# Sheet1.net
KiCad netlist of a schematic drawn in Altium Designer
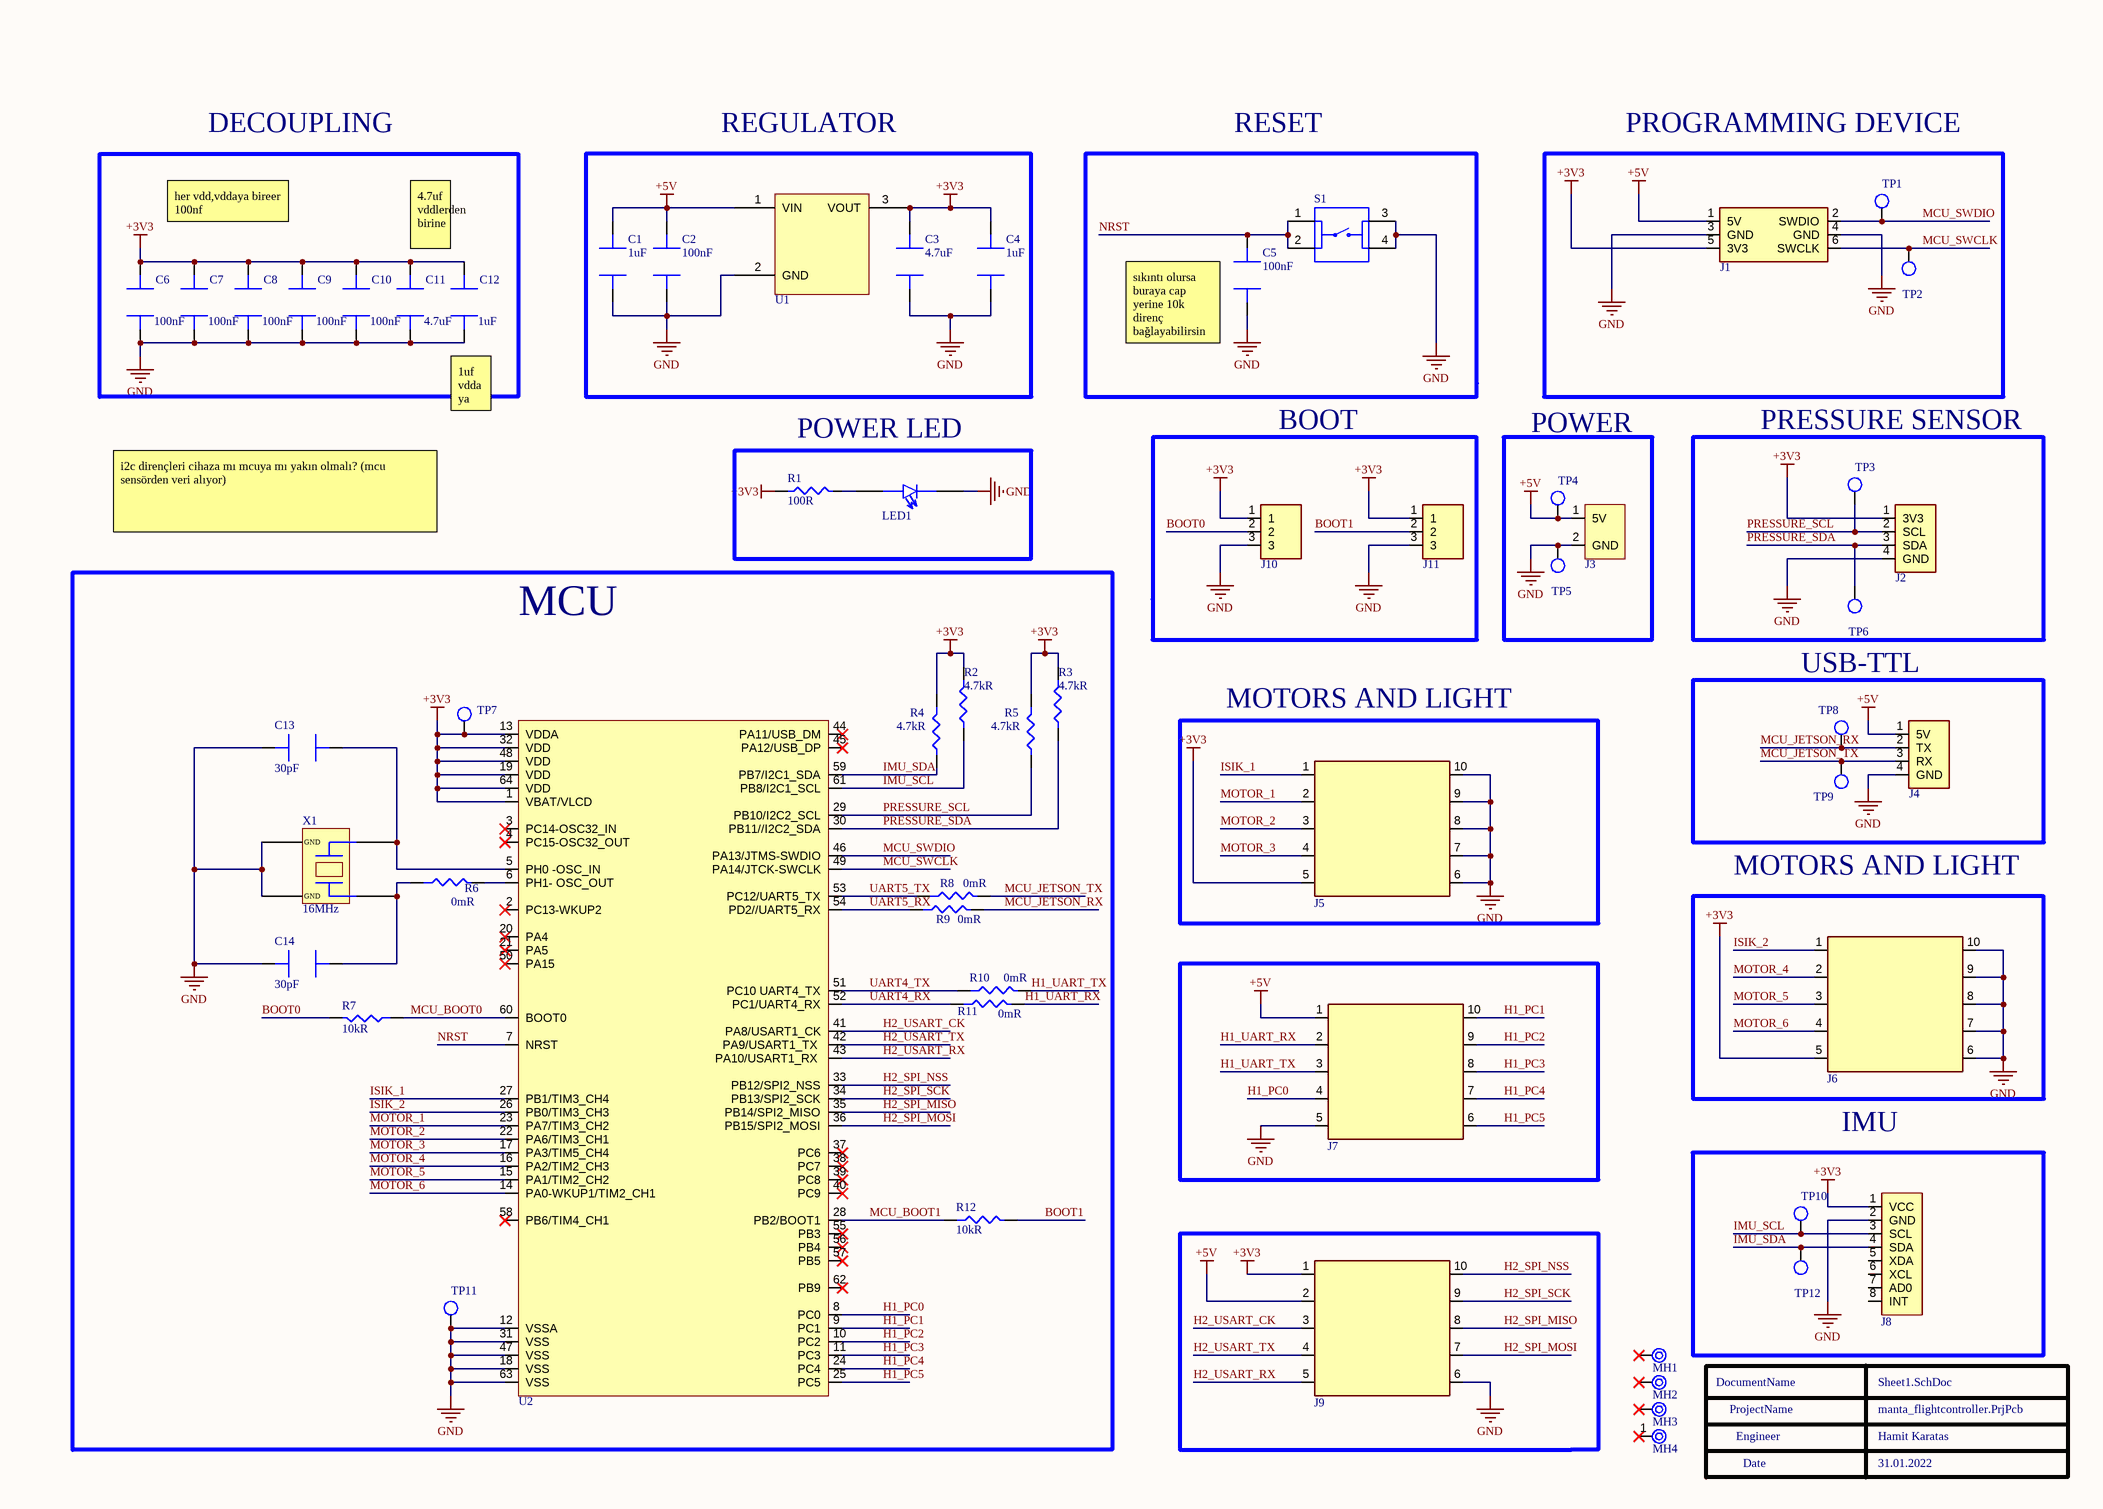
[diagram p0: Sheet1.SchDoc]

(export (version "E")
  (design (tool "Eeschema 10.0.6"))
  (components
    (comp (ref "C1")
      (value "CAP CER 1uF 0805")
      (footprint "cap_0805")
      (description "0805 0.1 uF ±10 % Tolerance 50 V X7R Multilayer Ceramic Capacitors")
      (fields
        (field (name "MANUFACTURER") "Samsung")
        (field (name "MANUFACTURER PART NUMBER") "CL21B104KBFNNNE")
        (field (name "CAPACITANCE") "1uF")
        (field (name "DESIGNED BY") "Hamit")
      )
      (libsource (lib "altium_giris") (part "CAP CER 1uF 0805"))
    )
    (comp (ref "C2")
      (value "CL21B104KBCNNNC")
      (footprint "cap_0805")
      (fields
        (field (name "MANUFACTURER") "Samsung")
        (field (name "TOLERANCE") "10%")
        (field (name "VOLTAGE") "50V")
        (field (name "CAPACITANCE") "100nF")
        (field (name "DESIGNED BY") "Hamit")
      )
      (libsource (lib "altium_giris") (part "CAP cer 100nF 0805"))
    )
    (comp (ref "C3")
      (value "CL21A475KAQNNNE")
      (footprint "cap_0805")
      (fields
        (field (name "MANUFACTURER") "Samsung")
        (field (name "TOLERANCE") "10%")
        (field (name "CAPACITANCE") "4.7uF")
        (field (name "DESIGNED BY") "Hamit")
      )
      (libsource (lib "altium_giris") (part "CAP_0805_4.7uF"))
    )
    (comp (ref "C4")
      (value "CAP CER 1uF 0805")
      (footprint "cap_0805")
      (description "0805 0.1 uF ±10 % Tolerance 50 V X7R Multilayer Ceramic Capacitors")
      (fields
        (field (name "MANUFACTURER") "Samsung")
        (field (name "MANUFACTURER PART NUMBER") "CL21B104KBFNNNE")
        (field (name "CAPACITANCE") "1uF")
        (field (name "DESIGNED BY") "Hamit")
      )
      (libsource (lib "altium_giris") (part "CAP CER 1uF 0805"))
    )
    (comp (ref "C5")
      (value "CAP CER 100nF 0603")
      (footprint "CAP_0603")
      (fields
        (field (name "MANUFACTURER") "KEMET")
        (field (name "MANUFACTURER PART NUMBER") "C0603C104K5RACTU")
        (field (name "TOLERANCE") "10%")
        (field (name "CAPACITANCE") "100nF")
        (field (name "DESIGNED BY") "Hamit")
      )
      (libsource (lib "altium_giris") (part "CAP CER 100nF 0603"))
    )
    (comp (ref "C6")
      (value "CAP CER 100nF 0603")
      (footprint "CAP_0603")
      (fields
        (field (name "MANUFACTURER") "KEMET")
        (field (name "MANUFACTURER PART NUMBER") "C0603C104K5RACTU")
        (field (name "TOLERANCE") "10%")
        (field (name "CAPACITANCE") "100nF")
        (field (name "DESIGNED BY") "Hamit")
      )
      (libsource (lib "altium_giris") (part "CAP CER 100nF 0603"))
    )
    (comp (ref "C7")
      (value "CAP CER 100nF 0603")
      (footprint "CAP_0603")
      (fields
        (field (name "MANUFACTURER") "KEMET")
        (field (name "MANUFACTURER PART NUMBER") "C0603C104K5RACTU")
        (field (name "TOLERANCE") "10%")
        (field (name "CAPACITANCE") "100nF")
        (field (name "DESIGNED BY") "Hamit")
      )
      (libsource (lib "altium_giris") (part "CAP CER 100nF 0603"))
    )
    (comp (ref "C8")
      (value "CAP CER 100nF 0603")
      (footprint "CAP_0603")
      (fields
        (field (name "MANUFACTURER") "KEMET")
        (field (name "MANUFACTURER PART NUMBER") "C0603C104K5RACTU")
        (field (name "TOLERANCE") "10%")
        (field (name "CAPACITANCE") "100nF")
        (field (name "DESIGNED BY") "Hamit")
      )
      (libsource (lib "altium_giris") (part "CAP CER 100nF 0603"))
    )
    (comp (ref "C9")
      (value "CAP CER 100nF 0603")
      (footprint "CAP_0603")
      (fields
        (field (name "MANUFACTURER") "KEMET")
        (field (name "MANUFACTURER PART NUMBER") "C0603C104K5RACTU")
        (field (name "TOLERANCE") "10%")
        (field (name "CAPACITANCE") "100nF")
        (field (name "DESIGNED BY") "Hamit")
      )
      (libsource (lib "altium_giris") (part "CAP CER 100nF 0603"))
    )
    (comp (ref "C10")
      (value "CAP CER 100nF 0603")
      (footprint "CAP_0603")
      (fields
        (field (name "MANUFACTURER") "KEMET")
        (field (name "MANUFACTURER PART NUMBER") "C0603C104K5RACTU")
        (field (name "TOLERANCE") "10%")
        (field (name "CAPACITANCE") "100nF")
        (field (name "DESIGNED BY") "Hamit")
      )
      (libsource (lib "altium_giris") (part "CAP CER 100nF 0603"))
    )
    (comp (ref "C11")
      (value "CL21A475KAQNNNE")
      (footprint "cap_0805")
      (fields
        (field (name "MANUFACTURER") "Samsung")
        (field (name "TOLERANCE") "10%")
        (field (name "CAPACITANCE") "4.7uF")
        (field (name "DESIGNED BY") "Hamit")
      )
      (libsource (lib "altium_giris") (part "CAP CER 4.7 uF"))
    )
    (comp (ref "C12")
      (value "CAP CER 1uF 0805")
      (footprint "cap_0805")
      (description "0805 0.1 uF ±10 % Tolerance 50 V X7R Multilayer Ceramic Capacitors")
      (fields
        (field (name "MANUFACTURER") "Samsung")
        (field (name "MANUFACTURER PART NUMBER") "CL21B104KBFNNNE")
        (field (name "CAPACITANCE") "1uF")
        (field (name "DESIGNED BY") "Hamit")
      )
      (libsource (lib "altium_giris") (part "CAP CER 1uF 0805"))
    )
    (comp (ref "C13")
      (value "C0805C300M5HAC7800")
      (footprint "cap_0805")
      (description "Cap Cer 0805 30PF 50V Ultra Stab")
      (fields (field (name "MANUFACTURER") "KEMET") (field (name "CAPACITANCE") "30pF"))
      (libsource (lib "altium_giris") (part "CAP CER 30 PF 0805"))
    )
    (comp (ref "C14")
      (value "C0805C300M5HAC7800")
      (footprint "cap_0805")
      (description "Cap Cer 0805 30PF 50V Ultra Stab")
      (fields (field (name "MANUFACTURER") "KEMET") (field (name "CAPACITANCE") "30pF"))
      (libsource (lib "altium_giris") (part "CAP CER 30 PF 0805"))
    )
    (comp (ref "J1")
      (value "67997-206HLF")
      (footprint "CONN 6 PINS 2 ROWS")
      (description "Conn Unshrouded Header HDR 6 POS 2.54mm Solder ST Top Entry Thru-Hole BergStik® Bulk")
      (fields (field (name "MANUFACTURER") "ICC"))
      (libsource (lib "altium_giris") (part "CONN 6 PIN 2 ROWS"))
    )
    (comp (ref "J2")
      (value "61300411121")
      (footprint "CONN 4PINS 1 ROW")
      (description "CONN HEADER 4 POS 2.54")
      (fields (field (name "MANUFACTURER") "Wurth Electronics"))
      (libsource (lib "altium_giris") (part "CONN 4 PINS 1 ROW"))
    )
    (comp (ref "J3")
      (value "TERMINAL BLOCK, PLUGGABLE, 5.08,")
      (footprint "TBP01R1-508-02BE")
      (description "Conn Shrouded Header HDR 2 POS 5.08mm Solder RA Side Entry Thru-Hole Bag")
      (fields
        (field (name "MANUFACTURER") "CUI")
        (field (name "MANUFACTURER PART NUMBER") "TBP01R1-508-02BE")
        (field (name "DESIGNED BY") "Hamit")
      )
      (libsource (lib "altium_giris") (part "TERMINAL BLOCK TBP01R1-508-02BE"))
    )
    (comp (ref "J4")
      (value "61300411121")
      (footprint "CONN 4PINS 1 ROW")
      (description "CONN HEADER 4 POS 2.54")
      (fields (field (name "MANUFACTURER") "Wurth Electronics"))
      (libsource (lib "altium_giris") (part "CONN 4 PINS 1 ROW"))
    )
    (comp (ref "J5")
      (value "302-S101")
      (footprint "CONN 10 PINS 2 ROWS")
      (description "10 pin 接头，有罩 连接器 0.100&quot;（2.54mm） 通孔 金")
      (fields (field (name "MANUFACTURER") "On-Shore Technology"))
      (libsource (lib "altium_giris") (part "CONN 10 PINS"))
    )
    (comp (ref "J6")
      (value "302-S101")
      (footprint "CONN 10 PINS 2 ROWS")
      (description "10 pin 接头，有罩 连接器 0.100&quot;（2.54mm） 通孔 金")
      (fields (field (name "MANUFACTURER") "On-Shore Technology"))
      (libsource (lib "altium_giris") (part "CONN 10 PINS"))
    )
    (comp (ref "J7")
      (value "302-S101")
      (footprint "CONN 10 PINS 2 ROWS")
      (description "10 pin 接头，有罩 连接器 0.100&quot;（2.54mm） 通孔 金")
      (fields (field (name "MANUFACTURER") "On-Shore Technology"))
      (libsource (lib "altium_giris") (part "CONN 10 PINS"))
    )
    (comp (ref "J8")
      (value "CONN 8 PIN")
      (footprint "CONN 8 PINS TH 2.54mm")
      (libsource (lib "altium_giris") (part "CONN 8 PIN"))
    )
    (comp (ref "J9")
      (value "302-S101")
      (footprint "CONN 10 PINS 2 ROWS")
      (description "10 pin 接头，有罩 连接器 0.100&quot;（2.54mm） 通孔 金")
      (fields (field (name "MANUFACTURER") "On-Shore Technology"))
      (libsource (lib "altium_giris") (part "CONN 10 PINS"))
    )
    (comp (ref "J10")
      (value "Conn Header HDR 3 POS 2.54mm")
      (footprint "CONN 3 PINS")
      (description "Conn Unshrouded Header HDR 3 POS 2.54mm Solder ST Top Entry Thru-Hole BergStik® Bulk")
      (fields
        (field (name "MANUFACTURER") "Amphenol ICC / FCI")
        (field (name "MANUFACTURER PART NUMBER") "68001-203HLF")
      )
      (libsource (lib "altium_giris") (part "CONN 3 PINS"))
    )
    (comp (ref "J11")
      (value "Conn Header HDR 3 POS 2.54mm")
      (footprint "CONN 3 PINS")
      (description "Conn Unshrouded Header HDR 3 POS 2.54mm Solder ST Top Entry Thru-Hole BergStik® Bulk")
      (fields
        (field (name "MANUFACTURER") "Amphenol ICC / FCI")
        (field (name "MANUFACTURER PART NUMBER") "68001-203HLF")
      )
      (libsource (lib "altium_giris") (part "CONN 3 PINS"))
    )
    (comp (ref "LED1")
      (value "LTST-C171GKT")
      (footprint "LED GREEN 0805")
      (description "Green 0805 130 º Min 5 mcd Typical 12 mcd Water Clear Lens SMT LED")
      (fields (field (name "MANUFACTURER") "Vishay Lite-On") (field (name "DESIGNED BY") "Hamit"))
      (libsource (lib "altium_giris") (part "LED GREEN 0805"))
    )
    (comp (ref "MH1")
      (value "MOUNTING HOLE")
      (footprint "MOUNTING HOLE")
      (libsource (lib "altium_giris") (part "MOUNTING HOLE"))
    )
    (comp (ref "MH2")
      (value "MOUNTING HOLE")
      (footprint "MOUNTING HOLE")
      (libsource (lib "altium_giris") (part "MOUNTING HOLE"))
    )
    (comp (ref "MH3")
      (value "MOUNTING HOLE")
      (footprint "MOUNTING HOLE")
      (libsource (lib "altium_giris") (part "MOUNTING HOLE"))
    )
    (comp (ref "MH4")
      (value "MOUNTING HOLE")
      (footprint "MOUNTING HOLE")
      (libsource (lib "") (part "MOUNTING HOLE_1"))
    )
    (comp (ref "R1")
      (value "RC0603FR-7W100RL")
      (footprint "RES_0603")
      (description "RESISTOR, 0603, 100R, 1%")
      (fields
        (field (name "MANUFACTURER") "Yageo")
        (field (name "TOLERANCE") "1%")
        (field (name "RESISTANCE") "100R")
      )
      (libsource (lib "altium_giris") (part "RES 100 OHM 0603"))
    )
    (comp (ref "R2")
      (value "RC0603JR-074K7L")
      (footprint "res_1206")
      (description "Res Thick Film 0603 4.7K Ohm 5% 0.1W(1/10W) ±100ppm/C Molded SMD Paper T/R")
      (fields
        (field (name "MANUFACTURER") "Yageo")
        (field (name "TOLERANCE") "5%")
        (field (name "RESISTANCE") "4.7kR")
        (field (name "DESIGNED BY") "Hamit")
      )
      (libsource (lib "altium_giris") (part "RES 4K7 OHM"))
    )
    (comp (ref "R3")
      (value "RC0603JR-074K7L")
      (footprint "res_1206")
      (description "Res Thick Film 0603 4.7K Ohm 5% 0.1W(1/10W) ±100ppm/C Molded SMD Paper T/R")
      (fields
        (field (name "MANUFACTURER") "Yageo")
        (field (name "TOLERANCE") "5%")
        (field (name "RESISTANCE") "4.7kR")
        (field (name "DESIGNED BY") "Hamit")
      )
      (libsource (lib "altium_giris") (part "RES 4K7 OHM"))
    )
    (comp (ref "R4")
      (value "RC0603JR-074K7L")
      (footprint "res_1206")
      (description "Res Thick Film 0603 4.7K Ohm 5% 0.1W(1/10W) ±100ppm/C Molded SMD Paper T/R")
      (fields
        (field (name "MANUFACTURER") "Yageo")
        (field (name "TOLERANCE") "5%")
        (field (name "RESISTANCE") "4.7kR")
        (field (name "DESIGNED BY") "Hamit")
      )
      (libsource (lib "altium_giris") (part "RES 4K7 OHM"))
    )
    (comp (ref "R5")
      (value "RC0603JR-074K7L")
      (footprint "res_1206")
      (description "Res Thick Film 0603 4.7K Ohm 5% 0.1W(1/10W) ±100ppm/C Molded SMD Paper T/R")
      (fields
        (field (name "MANUFACTURER") "Yageo")
        (field (name "TOLERANCE") "5%")
        (field (name "RESISTANCE") "4.7kR")
        (field (name "DESIGNED BY") "Hamit")
      )
      (libsource (lib "altium_giris") (part "RES 4K7 OHM"))
    )
    (comp (ref "R6")
      (value "RC0603JR-070RL")
      (footprint "RES_0603")
      (description "RES SMD 0 OHM JUMPER 1/10W 0603")
      (fields
        (field (name "MANUFACTURER") "Yageo")
        (field (name "TOLERANCE") "1%")
        (field (name "RESISTANCE") "0mR")
        (field (name "DESIGNED BY") "Hamit")
      )
      (libsource (lib "altium_giris") (part "RES 0 ohm 0603"))
    )
    (comp (ref "R7")
      (value "RES 10K OHM 0603")
      (footprint "RES_0603")
      (description "Res General Purpose Thick Film 0603 10K Ohm 1% 1/10W ±100ppm/°C Molded SMD Paper T/R")
      (fields
        (field (name "MANUFACTURER") "Yageo")
        (field (name "MANUFACTURER PART NUMBER") "RC0603FR-0710KL")
        (field (name "RESISTANCE") "10kR")
        (field (name "DESIGNED BY") "Hamit")
      )
      (libsource (lib "altium_giris") (part "RES 10K OHM 0603"))
    )
    (comp (ref "R8")
      (value "RC0603JR-070RL")
      (footprint "RES_0603")
      (description "RES SMD 0 OHM JUMPER 1/10W 0603")
      (fields
        (field (name "MANUFACTURER") "Yageo")
        (field (name "TOLERANCE") "1%")
        (field (name "RESISTANCE") "0mR")
        (field (name "DESIGNED BY") "Hamit")
      )
      (libsource (lib "altium_giris") (part "RES 0 ohm 0603"))
    )
    (comp (ref "R9")
      (value "RC0603JR-070RL")
      (footprint "RES_0603")
      (description "RES SMD 0 OHM JUMPER 1/10W 0603")
      (fields
        (field (name "MANUFACTURER") "Yageo")
        (field (name "TOLERANCE") "1%")
        (field (name "RESISTANCE") "0mR")
        (field (name "DESIGNED BY") "Hamit")
      )
      (libsource (lib "altium_giris") (part "RES 0 ohm 0603"))
    )
    (comp (ref "R10")
      (value "RC0603JR-070RL")
      (footprint "RES_0603")
      (description "RES SMD 0 OHM JUMPER 1/10W 0603")
      (fields
        (field (name "MANUFACTURER") "Yageo")
        (field (name "TOLERANCE") "1%")
        (field (name "RESISTANCE") "0mR")
        (field (name "DESIGNED BY") "Hamit")
      )
      (libsource (lib "altium_giris") (part "RES 0 ohm 0603"))
    )
    (comp (ref "R11")
      (value "RC0603JR-070RL")
      (footprint "RES_0603")
      (description "RES SMD 0 OHM JUMPER 1/10W 0603")
      (fields
        (field (name "MANUFACTURER") "Yageo")
        (field (name "TOLERANCE") "1%")
        (field (name "RESISTANCE") "0mR")
        (field (name "DESIGNED BY") "Hamit")
      )
      (libsource (lib "altium_giris") (part "RES 0 ohm 0603"))
    )
    (comp (ref "R12")
      (value "RES 10K OHM 0603")
      (footprint "RES_0603")
      (description "Res General Purpose Thick Film 0603 10K Ohm 1% 1/10W ±100ppm/°C Molded SMD Paper T/R")
      (fields
        (field (name "MANUFACTURER") "Yageo")
        (field (name "MANUFACTURER PART NUMBER") "RC0603FR-0710KL")
        (field (name "RESISTANCE") "10kR")
        (field (name "DESIGNED BY") "Hamit")
      )
      (libsource (lib "altium_giris") (part "RES 10K OHM 0603"))
    )
    (comp (ref "S1")
      (value "1825910-6")
      (footprint "button")
      (description "Switch Tactile OFF (ON) SPST Round Button PC Pins 0.05A 24VDC 1.57N Thru-Hole Loose")
      (fields (field (name "MANUFACTURER") "TE Connectivity Alcoswitch"))
      (libsource (lib "altium_giris") (part "button 4 pads"))
    )
    (comp (ref "TP1")
      (value "TEST_POINT")
      (footprint "TEST POINT")
      (libsource (lib "altium_giris") (part "TEST POINT"))
    )
    (comp (ref "TP2")
      (value "TEST_POINT")
      (footprint "TEST POINT")
      (libsource (lib "altium_giris") (part "TEST POINT"))
    )
    (comp (ref "TP3")
      (value "TEST_POINT")
      (footprint "TEST POINT")
      (libsource (lib "altium_giris") (part "TEST POINT"))
    )
    (comp (ref "TP4")
      (value "TEST_POINT")
      (footprint "TEST POINT")
      (libsource (lib "altium_giris") (part "TEST POINT"))
    )
    (comp (ref "TP5")
      (value "TEST_POINT")
      (footprint "TEST POINT")
      (libsource (lib "altium_giris") (part "TEST POINT"))
    )
    (comp (ref "TP6")
      (value "TEST_POINT")
      (footprint "TEST POINT")
      (libsource (lib "altium_giris") (part "TEST POINT"))
    )
    (comp (ref "TP7")
      (value "TEST_POINT")
      (footprint "TEST POINT")
      (libsource (lib "altium_giris") (part "TEST POINT"))
    )
    (comp (ref "TP8")
      (value "TEST_POINT")
      (footprint "TEST POINT")
      (libsource (lib "altium_giris") (part "TEST POINT"))
    )
    (comp (ref "TP9")
      (value "TEST_POINT")
      (footprint "TEST POINT")
      (libsource (lib "altium_giris") (part "TEST POINT"))
    )
    (comp (ref "TP10")
      (value "TEST_POINT")
      (footprint "TEST POINT")
      (libsource (lib "altium_giris") (part "TEST POINT"))
    )
    (comp (ref "TP11")
      (value "TEST_POINT")
      (footprint "TEST POINT")
      (libsource (lib "altium_giris") (part "TEST POINT"))
    )
    (comp (ref "TP12")
      (value "TEST_POINT")
      (footprint "TEST POINT")
      (libsource (lib "altium_giris") (part "TEST POINT"))
    )
    (comp (ref "U1")
      (value "AP7361-33E-13")
      (footprint "AP7361-33E-13")
      (description "LDO Regulator Pos 3.3V 1A 4-Pin(3+Tab) SOT-223 T/R")
      (fields (field (name "MANUFACTURER") "Diodes") (field (name "DESIGNED BY") "Hamit"))
      (libsource (lib "altium_giris") (part "REGULATOR AP7361-33E-13"))
    )
    (comp (ref "U2")
      (value "STM32L152RET6")
      (footprint "STM32L152RET6")
      (description "Ultra-low-power ARM Cortex-M3 MCU with 512 Kbytes Flash, 32 MHz CPU, USB, 2xOp-amp")
      (fields (field (name "MANUFACTURER") "STMicroelectronics"))
      (libsource (lib "altium_giris") (part "STM32L152RET6"))
    )
    (comp (ref "X1")
      (value "ECS-160-20-30B-TR")
      (footprint "CRYSTAL_ECS-160-20-30B-TR")
      (description "CRYSTAL 16.0000MHZ 20PF SMD")
      (fields
        (field (name "MANUFACTURER") "ECS International")
        (field (name "TOLERANCE") "50ppm")
        (field (name "FREQUENCY") "16MHz")
        (field (name "DESIGNED BY") "Hamit")
      )
      (libsource (lib "altium_giris") (part "CRYSTAL 16MHZ 20PF SMD"))
    )
  )
  (nets
    (net (code "1") (name "+3V3") (class "Default")
      (node (ref "C10") (pin "2") (pinfunction "2_2") (pintype "passive"))
      (node (ref "C11") (pin "2") (pinfunction "2_2") (pintype "passive"))
      (node (ref "C12") (pin "2") (pinfunction "2_2") (pintype "passive"))
      (node (ref "C3") (pin "2") (pinfunction "2_2") (pintype "passive"))
      (node (ref "C4") (pin "2") (pinfunction "2_2") (pintype "passive"))
      (node (ref "C6") (pin "2") (pinfunction "2_2") (pintype "passive"))
      (node (ref "C7") (pin "2") (pinfunction "2_2") (pintype "passive"))
      (node (ref "C8") (pin "2") (pinfunction "2_2") (pintype "passive"))
      (node (ref "C9") (pin "2") (pinfunction "2_2") (pintype "passive"))
      (node (ref "J1") (pin "5") (pinfunction "3V3_5") (pintype "passive"))
      (node (ref "J10") (pin "1") (pinfunction "1_1") (pintype "passive"))
      (node (ref "J11") (pin "1") (pinfunction "1_1") (pintype "passive"))
      (node (ref "J2") (pin "1") (pinfunction "3V3_1") (pintype "passive"))
      (node (ref "J5") (pin "5") (pinfunction "5_5") (pintype "passive"))
      (node (ref "J6") (pin "5") (pinfunction "5_5") (pintype "passive"))
      (node (ref "J8") (pin "1") (pinfunction "VCC_1") (pintype "passive"))
      (node (ref "J9") (pin "1") (pinfunction "1_1") (pintype "passive"))
      (node (ref "R1") (pin "2") (pinfunction "2_2") (pintype "passive"))
      (node (ref "R2") (pin "0") (pinfunction "0_0") (pintype "passive"))
      (node (ref "R3") (pin "0") (pinfunction "0_0") (pintype "passive"))
      (node (ref "R4") (pin "0") (pinfunction "0_0") (pintype "passive"))
      (node (ref "R5") (pin "0") (pinfunction "0_0") (pintype "passive"))
      (node (ref "TP7") (pin "1") (pinfunction "TP_1") (pintype "passive"))
      (node (ref "U1") (pin "3") (pinfunction "VOUT_3") (pintype "passive"))
      (node (ref "U2") (pin "1") (pinfunction "VBAT/VLCD_1") (pintype "passive"))
      (node (ref "U2") (pin "13") (pinfunction "VDDA_13") (pintype "passive"))
      (node (ref "U2") (pin "19") (pinfunction "VDD_19") (pintype "passive"))
      (node (ref "U2") (pin "32") (pinfunction "VDD_32") (pintype "passive"))
      (node (ref "U2") (pin "48") (pinfunction "VDD_48") (pintype "passive"))
      (node (ref "U2") (pin "64") (pinfunction "VDD_64") (pintype "passive"))
    )
    (net (code "2") (name "+5V") (class "Default")
      (node (ref "C1") (pin "2") (pinfunction "2_2") (pintype "passive"))
      (node (ref "C2") (pin "2") (pinfunction "2_2") (pintype "passive"))
      (node (ref "J1") (pin "1") (pinfunction "5V_1") (pintype "passive"))
      (node (ref "J3") (pin "1") (pinfunction "5V_1") (pintype "power_in"))
      (node (ref "J4") (pin "1") (pinfunction "3V3_1") (pintype "passive"))
      (node (ref "J7") (pin "1") (pinfunction "1_1") (pintype "passive"))
      (node (ref "J9") (pin "2") (pinfunction "2_2") (pintype "passive"))
      (node (ref "TP4") (pin "1") (pinfunction "TP_1") (pintype "passive"))
      (node (ref "U1") (pin "1") (pinfunction "VIN_1") (pintype "passive"))
    )
    (net (code "3") (name "/BOOT0") (class "Default")
      (node (ref "J10") (pin "2") (pinfunction "2_2") (pintype "passive"))
      (node (ref "R7") (pin "2") (pinfunction "2_2") (pintype "passive"))
    )
    (net (code "4") (name "/BOOT1") (class "Default")
      (node (ref "J11") (pin "2") (pinfunction "2_2") (pintype "passive"))
      (node (ref "R12") (pin "2") (pinfunction "2_2") (pintype "passive"))
    )
    (net (code "5") (name "/H1_PC0") (class "Default")
      (node (ref "J7") (pin "4") (pinfunction "4_4") (pintype "passive"))
      (node (ref "U2") (pin "8") (pinfunction "PC0_8") (pintype "passive"))
    )
    (net (code "6") (name "/H1_PC1") (class "Default")
      (node (ref "J7") (pin "10") (pinfunction "10_10") (pintype "passive"))
      (node (ref "U2") (pin "9") (pinfunction "PC1_9") (pintype "passive"))
    )
    (net (code "7") (name "/H1_PC2") (class "Default")
      (node (ref "J7") (pin "9") (pinfunction "9_9") (pintype "passive"))
      (node (ref "U2") (pin "10") (pinfunction "PC2_10") (pintype "passive"))
    )
    (net (code "8") (name "/H1_PC3") (class "Default")
      (node (ref "J7") (pin "8") (pinfunction "8_8") (pintype "passive"))
      (node (ref "U2") (pin "11") (pinfunction "PC3_11") (pintype "passive"))
    )
    (net (code "9") (name "/H1_PC4") (class "Default")
      (node (ref "J7") (pin "7") (pinfunction "7_7") (pintype "passive"))
      (node (ref "U2") (pin "24") (pinfunction "PC4_24") (pintype "passive"))
    )
    (net (code "10") (name "/H1_PC5") (class "Default")
      (node (ref "J7") (pin "6") (pinfunction "6_6") (pintype "passive"))
      (node (ref "U2") (pin "25") (pinfunction "PC5_25") (pintype "passive"))
    )
    (net (code "11") (name "/H1_UART_RX") (class "Default")
      (node (ref "J7") (pin "2") (pinfunction "2_2") (pintype "passive"))
      (node (ref "R11") (pin "2") (pinfunction "2_2") (pintype "passive"))
    )
    (net (code "12") (name "/H1_UART_TX") (class "Default")
      (node (ref "J7") (pin "3") (pinfunction "3_3") (pintype "passive"))
      (node (ref "R10") (pin "2") (pinfunction "2_2") (pintype "passive"))
    )
    (net (code "13") (name "/H2_SPI_MISO") (class "Default")
      (node (ref "J9") (pin "8") (pinfunction "8_8") (pintype "passive"))
      (node (ref "U2") (pin "35") (pinfunction "PB14/SPI2_MISO_35") (pintype "passive"))
    )
    (net (code "14") (name "/H2_SPI_MOSI") (class "Default")
      (node (ref "J9") (pin "7") (pinfunction "7_7") (pintype "passive"))
      (node (ref "U2") (pin "36") (pinfunction "PB15/SPI2_MOSI_36") (pintype "passive"))
    )
    (net (code "15") (name "/H2_SPI_NSS") (class "Default")
      (node (ref "J9") (pin "10") (pinfunction "10_10") (pintype "passive"))
      (node (ref "U2") (pin "33") (pinfunction "PB12/SPI2_NSS_33") (pintype "passive"))
    )
    (net (code "16") (name "/H2_SPI_SCK") (class "Default")
      (node (ref "J9") (pin "9") (pinfunction "9_9") (pintype "passive"))
      (node (ref "U2") (pin "34") (pinfunction "PB13/SPI2_SCK_34") (pintype "passive"))
    )
    (net (code "17") (name "/H2_USART_CK") (class "Default")
      (node (ref "J9") (pin "3") (pinfunction "3_3") (pintype "passive"))
      (node (ref "U2") (pin "41") (pinfunction "PA8/USART1_CK_41") (pintype "passive"))
    )
    (net (code "18") (name "/H2_USART_RX") (class "Default")
      (node (ref "J9") (pin "5") (pinfunction "5_5") (pintype "passive"))
      (node (ref "U2") (pin "43") (pinfunction "PA10/USART1_RX_43") (pintype "passive"))
    )
    (net (code "19") (name "/H2_USART_TX") (class "Default")
      (node (ref "J9") (pin "4") (pinfunction "4_4") (pintype "passive"))
      (node (ref "U2") (pin "42") (pinfunction "PA9/USART1_TX_42") (pintype "passive"))
    )
    (net (code "20") (name "/IMU_SCL") (class "Default")
      (node (ref "J8") (pin "3") (pinfunction "SCL_3") (pintype "passive"))
      (node (ref "R2") (pin "1") (pinfunction "1_1") (pintype "passive"))
      (node (ref "TP10") (pin "1") (pinfunction "TP_1") (pintype "passive"))
      (node (ref "U2") (pin "61") (pinfunction "PB8/I2C1_SCL_61") (pintype "passive"))
    )
    (net (code "21") (name "/IMU_SDA") (class "Default")
      (node (ref "J8") (pin "4") (pinfunction "SDA_4") (pintype "passive"))
      (node (ref "R4") (pin "1") (pinfunction "1_1") (pintype "passive"))
      (node (ref "TP12") (pin "1") (pinfunction "TP_1") (pintype "passive"))
      (node (ref "U2") (pin "59") (pinfunction "PB7/I2C1_SDA_59") (pintype "passive"))
    )
    (net (code "22") (name "/ISIK_1") (class "Default")
      (node (ref "J5") (pin "1") (pinfunction "1_1") (pintype "passive"))
      (node (ref "U2") (pin "27") (pinfunction "PB1/TIM3_CH4_27") (pintype "passive"))
    )
    (net (code "23") (name "/ISIK_2") (class "Default")
      (node (ref "J6") (pin "1") (pinfunction "1_1") (pintype "passive"))
      (node (ref "U2") (pin "26") (pinfunction "PB0/TIM3_CH3_26") (pintype "passive"))
    )
    (net (code "24") (name "/MCU_BOOT0") (class "Default")
      (node (ref "R7") (pin "1") (pinfunction "1_1") (pintype "passive"))
      (node (ref "U2") (pin "60") (pinfunction "BOOT0_60") (pintype "passive"))
    )
    (net (code "25") (name "/MCU_BOOT1") (class "Default")
      (node (ref "R12") (pin "1") (pinfunction "1_1") (pintype "passive"))
      (node (ref "U2") (pin "28") (pinfunction "PB2/BOOT1_28") (pintype "passive"))
    )
    (net (code "26") (name "/MCU_JETSON_RX") (class "Default")
      (node (ref "J4") (pin "2") (pinfunction "SCL_2") (pintype "passive"))
      (node (ref "R9") (pin "2") (pinfunction "2_2") (pintype "passive"))
      (node (ref "TP8") (pin "1") (pinfunction "TP_1") (pintype "passive"))
    )
    (net (code "27") (name "/MCU_JETSON_TX") (class "Default")
      (node (ref "J4") (pin "3") (pinfunction "SDA_3") (pintype "passive"))
      (node (ref "R8") (pin "2") (pinfunction "2_2") (pintype "passive"))
      (node (ref "TP9") (pin "1") (pinfunction "TP_1") (pintype "passive"))
    )
    (net (code "28") (name "/MCU_SWCLK") (class "Default")
      (node (ref "J1") (pin "6") (pinfunction "SWCLK_6") (pintype "passive"))
      (node (ref "TP2") (pin "1") (pinfunction "TP_1") (pintype "passive"))
      (node (ref "U2") (pin "49") (pinfunction "PA14/JTCK-SWCLK_49") (pintype "passive"))
    )
    (net (code "29") (name "/MCU_SWDIO") (class "Default")
      (node (ref "J1") (pin "2") (pinfunction "SWDIO_2") (pintype "passive"))
      (node (ref "TP1") (pin "1") (pinfunction "TP_1") (pintype "passive"))
      (node (ref "U2") (pin "46") (pinfunction "PA13/JTMS-SWDIO_46") (pintype "passive"))
    )
    (net (code "30") (name "/MOTOR_1") (class "Default")
      (node (ref "J5") (pin "2") (pinfunction "2_2") (pintype "passive"))
      (node (ref "U2") (pin "23") (pinfunction "PA7/TIM3_CH2_23") (pintype "passive"))
    )
    (net (code "31") (name "/MOTOR_2") (class "Default")
      (node (ref "J5") (pin "3") (pinfunction "3_3") (pintype "passive"))
      (node (ref "U2") (pin "22") (pinfunction "PA6/TIM3_CH1_22") (pintype "passive"))
    )
    (net (code "32") (name "/MOTOR_3") (class "Default")
      (node (ref "J5") (pin "4") (pinfunction "4_4") (pintype "passive"))
      (node (ref "U2") (pin "17") (pinfunction "PA3/TIM5_CH4_17") (pintype "passive"))
    )
    (net (code "33") (name "/MOTOR_4") (class "Default")
      (node (ref "J6") (pin "2") (pinfunction "2_2") (pintype "passive"))
      (node (ref "U2") (pin "16") (pinfunction "PA2/TIM2_CH3_16") (pintype "passive"))
    )
    (net (code "34") (name "/MOTOR_5") (class "Default")
      (node (ref "J6") (pin "3") (pinfunction "3_3") (pintype "passive"))
      (node (ref "U2") (pin "15") (pinfunction "PA1/TIM2_CH2_15") (pintype "passive"))
    )
    (net (code "35") (name "/MOTOR_6") (class "Default")
      (node (ref "J6") (pin "4") (pinfunction "4_4") (pintype "passive"))
      (node (ref "U2") (pin "14") (pinfunction "PA0-WKUP1/TIM2_CH1_14") (pintype "passive"))
    )
    (net (code "36") (name "/NRST") (class "Default")
      (node (ref "C5") (pin "2") (pinfunction "2_2") (pintype "passive"))
      (node (ref "S1") (pin "1") (pinfunction "1_1") (pintype "passive"))
      (node (ref "S1") (pin "2") (pinfunction "2_2") (pintype "passive"))
      (node (ref "U2") (pin "7") (pinfunction "NRST_7") (pintype "passive"))
    )
    (net (code "37") (name "/PRESSURE_SCL") (class "Default")
      (node (ref "J2") (pin "2") (pinfunction "SCL_2") (pintype "passive"))
      (node (ref "R5") (pin "1") (pinfunction "1_1") (pintype "passive"))
      (node (ref "TP3") (pin "1") (pinfunction "TP_1") (pintype "passive"))
      (node (ref "U2") (pin "29") (pinfunction "PB10/I2C2_SCL_29") (pintype "passive"))
    )
    (net (code "38") (name "/PRESSURE_SDA") (class "Default")
      (node (ref "J2") (pin "3") (pinfunction "SDA_3") (pintype "passive"))
      (node (ref "R3") (pin "1") (pinfunction "1_1") (pintype "passive"))
      (node (ref "TP6") (pin "1") (pinfunction "TP_1") (pintype "passive"))
      (node (ref "U2") (pin "30") (pinfunction "PB11//I2C2_SDA_30") (pintype "passive"))
    )
    (net (code "39") (name "/UART4_RX") (class "Default")
      (node (ref "R11") (pin "1") (pinfunction "1_1") (pintype "passive"))
      (node (ref "U2") (pin "52") (pinfunction "PC1/UART4_RX_52") (pintype "passive"))
    )
    (net (code "40") (name "/UART4_TX") (class "Default")
      (node (ref "R10") (pin "1") (pinfunction "1_1") (pintype "passive"))
      (node (ref "U2") (pin "51") (pinfunction "PC10_UART4_TX_51") (pintype "passive"))
    )
    (net (code "41") (name "/UART5_RX") (class "Default")
      (node (ref "R9") (pin "1") (pinfunction "1_1") (pintype "passive"))
      (node (ref "U2") (pin "54") (pinfunction "PD2//UART5_RX_54") (pintype "passive"))
    )
    (net (code "42") (name "/UART5_TX") (class "Default")
      (node (ref "R8") (pin "1") (pinfunction "1_1") (pintype "passive"))
      (node (ref "U2") (pin "53") (pinfunction "PC12/UART5_TX_53") (pintype "passive"))
    )
    (net (code "43") (name "GND") (class "Default")
      (node (ref "C1") (pin "1") (pinfunction "1_1") (pintype "passive"))
      (node (ref "C10") (pin "1") (pinfunction "1_1") (pintype "passive"))
      (node (ref "C11") (pin "1") (pinfunction "1_1") (pintype "passive"))
      (node (ref "C12") (pin "1") (pinfunction "1_1") (pintype "passive"))
      (node (ref "C13") (pin "1") (pinfunction "1_1") (pintype "passive"))
      (node (ref "C14") (pin "1") (pinfunction "1_1") (pintype "passive"))
      (node (ref "C2") (pin "1") (pinfunction "1_1") (pintype "passive"))
      (node (ref "C3") (pin "1") (pinfunction "1_1") (pintype "passive"))
      (node (ref "C4") (pin "1") (pinfunction "1_1") (pintype "passive"))
      (node (ref "C5") (pin "1") (pinfunction "1_1") (pintype "passive"))
      (node (ref "C6") (pin "1") (pinfunction "1_1") (pintype "passive"))
      (node (ref "C7") (pin "1") (pinfunction "1_1") (pintype "passive"))
      (node (ref "C8") (pin "1") (pinfunction "1_1") (pintype "passive"))
      (node (ref "C9") (pin "1") (pinfunction "1_1") (pintype "passive"))
      (node (ref "J1") (pin "3") (pinfunction "GND_3") (pintype "passive"))
      (node (ref "J1") (pin "4") (pinfunction "GND_4") (pintype "passive"))
      (node (ref "J10") (pin "3") (pinfunction "3_3") (pintype "passive"))
      (node (ref "J11") (pin "3") (pinfunction "3_3") (pintype "passive"))
      (node (ref "J2") (pin "4") (pinfunction "GND_4") (pintype "passive"))
      (node (ref "J3") (pin "2") (pinfunction "GND_2") (pintype "power_in"))
      (node (ref "J4") (pin "4") (pinfunction "GND_4") (pintype "passive"))
      (node (ref "J5") (pin "10") (pinfunction "10_10") (pintype "passive"))
      (node (ref "J5") (pin "6") (pinfunction "6_6") (pintype "passive"))
      (node (ref "J5") (pin "7") (pinfunction "7_7") (pintype "passive"))
      (node (ref "J5") (pin "8") (pinfunction "8_8") (pintype "passive"))
      (node (ref "J5") (pin "9") (pinfunction "9_9") (pintype "passive"))
      (node (ref "J6") (pin "10") (pinfunction "10_10") (pintype "passive"))
      (node (ref "J6") (pin "6") (pinfunction "6_6") (pintype "passive"))
      (node (ref "J6") (pin "7") (pinfunction "7_7") (pintype "passive"))
      (node (ref "J6") (pin "8") (pinfunction "8_8") (pintype "passive"))
      (node (ref "J6") (pin "9") (pinfunction "9_9") (pintype "passive"))
      (node (ref "J7") (pin "5") (pinfunction "5_5") (pintype "passive"))
      (node (ref "J8") (pin "2") (pinfunction "GND_2") (pintype "passive"))
      (node (ref "J9") (pin "6") (pinfunction "6_6") (pintype "passive"))
      (node (ref "LED1") (pin "C") (pinfunction "C_C") (pintype "passive"))
      (node (ref "S1") (pin "3") (pinfunction "3_3") (pintype "passive"))
      (node (ref "S1") (pin "4") (pinfunction "4_4") (pintype "passive"))
      (node (ref "TP11") (pin "1") (pinfunction "TP_1") (pintype "passive"))
      (node (ref "TP5") (pin "1") (pinfunction "TP_1") (pintype "passive"))
      (node (ref "U1") (pin "2") (pinfunction "GND_2") (pintype "passive"))
      (node (ref "U2") (pin "12") (pinfunction "VSSA_12") (pintype "passive"))
      (node (ref "U2") (pin "18") (pinfunction "VSS_18") (pintype "passive"))
      (node (ref "U2") (pin "31") (pinfunction "VSS_31") (pintype "passive"))
      (node (ref "U2") (pin "47") (pinfunction "VSS_47") (pintype "passive"))
      (node (ref "U2") (pin "63") (pinfunction "VSS_63") (pintype "passive"))
      (node (ref "X1") (pin "2") (pinfunction "GND_2") (pintype "passive"))
      (node (ref "X1") (pin "4") (pinfunction "GND_4") (pintype "passive"))
    )
    (net (code "44") (name "Net-(C14-Pad2)") (class "Default")
      (node (ref "C14") (pin "2") (pinfunction "2_2") (pintype "passive"))
      (node (ref "R6") (pin "1") (pinfunction "1_1") (pintype "passive"))
      (node (ref "X1") (pin "1") (pinfunction "1_1") (pintype "passive"))
    )
    (net (code "45") (name "Net-(LED1-PadA)") (class "Default")
      (node (ref "LED1") (pin "A") (pinfunction "A_A") (pintype "passive"))
      (node (ref "R1") (pin "1") (pinfunction "1_1") (pintype "passive"))
    )
    (net (code "46") (name "Net-(U2-PH0_-OSC_IN)") (class "Default")
      (node (ref "C13") (pin "2") (pinfunction "2_2") (pintype "passive"))
      (node (ref "U2") (pin "5") (pinfunction "PH0_-OSC_IN_5") (pintype "passive"))
      (node (ref "X1") (pin "3") (pinfunction "3_3") (pintype "passive"))
    )
    (net (code "47") (name "Net-(U2-PH1-_OSC_OUT)") (class "Default")
      (node (ref "R6") (pin "2") (pinfunction "2_2") (pintype "passive"))
      (node (ref "U2") (pin "6") (pinfunction "PH1-_OSC_OUT_6") (pintype "passive"))
    )
    (net (code "48") (name "unconnected-(J8-AD0-Pad7)") (class "Default")
      (node (ref "J8") (pin "7") (pinfunction "AD0_7") (pintype "passive"))
    )
    (net (code "49") (name "unconnected-(J8-INT-Pad8)") (class "Default")
      (node (ref "J8") (pin "8") (pinfunction "INT_8") (pintype "passive"))
    )
    (net (code "50") (name "unconnected-(J8-XCL-Pad6)") (class "Default")
      (node (ref "J8") (pin "6") (pinfunction "XCL_6") (pintype "passive"))
    )
    (net (code "51") (name "unconnected-(J8-XDA-Pad5)") (class "Default")
      (node (ref "J8") (pin "5") (pinfunction "XDA_5") (pintype "passive"))
    )
    (net (code "52") (name "unconnected-(MH1-Pad1)") (class "Default")
      (node (ref "MH1") (pin "1") (pinfunction "1_1") (pintype "passive+no_connect"))
    )
    (net (code "53") (name "unconnected-(MH2-Pad1)") (class "Default")
      (node (ref "MH2") (pin "1") (pinfunction "1_1") (pintype "passive+no_connect"))
    )
    (net (code "54") (name "unconnected-(MH3-Pad1)") (class "Default")
      (node (ref "MH3") (pin "1") (pinfunction "1_1") (pintype "passive+no_connect"))
    )
    (net (code "55") (name "unconnected-(MH4-Pad1)") (class "Default")
      (node (ref "MH4") (pin "1") (pinfunction "1_1") (pintype "passive+no_connect"))
    )
    (net (code "56") (name "unconnected-(U2-PA4-Pad20)") (class "Default")
      (node (ref "U2") (pin "20") (pinfunction "PA4_20") (pintype "passive+no_connect"))
    )
    (net (code "57") (name "unconnected-(U2-PA5-Pad21)") (class "Default")
      (node (ref "U2") (pin "21") (pinfunction "PA5_21") (pintype "passive+no_connect"))
    )
    (net (code "58") (name "unconnected-(U2-PA11{slash}USB_DM-Pad44)") (class "Default")
      (node (ref "U2") (pin "44") (pinfunction "PA11/USB_DM_44") (pintype "passive+no_connect"))
    )
    (net (code "59") (name "unconnected-(U2-PA12{slash}USB_DP-Pad45)") (class "Default")
      (node (ref "U2") (pin "45") (pinfunction "PA12/USB_DP_45") (pintype "passive+no_connect"))
    )
    (net (code "60") (name "unconnected-(U2-PA15-Pad50)") (class "Default")
      (node (ref "U2") (pin "50") (pinfunction "PA15_50") (pintype "passive+no_connect"))
    )
    (net (code "61") (name "unconnected-(U2-PB3-Pad55)") (class "Default")
      (node (ref "U2") (pin "55") (pinfunction "PB3_55") (pintype "passive+no_connect"))
    )
    (net (code "62") (name "unconnected-(U2-PB4-Pad56)") (class "Default")
      (node (ref "U2") (pin "56") (pinfunction "PB4_56") (pintype "passive+no_connect"))
    )
    (net (code "63") (name "unconnected-(U2-PB5-Pad57)") (class "Default")
      (node (ref "U2") (pin "57") (pinfunction "PB5_57") (pintype "passive+no_connect"))
    )
    (net (code "64") (name "unconnected-(U2-PB6{slash}TIM4_CH1-Pad58)") (class "Default")
      (node (ref "U2") (pin "58") (pinfunction "PB6/TIM4_CH1_58") (pintype "passive+no_connect"))
    )
    (net (code "65") (name "unconnected-(U2-PB9-Pad62)") (class "Default")
      (node (ref "U2") (pin "62") (pinfunction "PB9_62") (pintype "passive+no_connect"))
    )
    (net (code "66") (name "unconnected-(U2-PC6-Pad37)") (class "Default")
      (node (ref "U2") (pin "37") (pinfunction "PC6_37") (pintype "passive+no_connect"))
    )
    (net (code "67") (name "unconnected-(U2-PC7-Pad38)") (class "Default")
      (node (ref "U2") (pin "38") (pinfunction "PC7_38") (pintype "passive+no_connect"))
    )
    (net (code "68") (name "unconnected-(U2-PC8-Pad39)") (class "Default")
      (node (ref "U2") (pin "39") (pinfunction "PC8_39") (pintype "passive+no_connect"))
    )
    (net (code "69") (name "unconnected-(U2-PC9-Pad40)") (class "Default")
      (node (ref "U2") (pin "40") (pinfunction "PC9_40") (pintype "passive+no_connect"))
    )
    (net (code "70") (name "unconnected-(U2-PC13-WKUP2-Pad2)") (class "Default")
      (node (ref "U2") (pin "2") (pinfunction "PC13-WKUP2_2") (pintype "passive+no_connect"))
    )
    (net (code "71") (name "unconnected-(U2-PC14-OSC32_IN-Pad3)") (class "Default")
      (node (ref "U2") (pin "3") (pinfunction "PC14-OSC32_IN_3") (pintype "passive+no_connect"))
    )
    (net (code "72") (name "unconnected-(U2-PC15-OSC32_OUT-Pad4)") (class "Default")
      (node (ref "U2") (pin "4") (pinfunction "PC15-OSC32_OUT_4") (pintype "passive+no_connect"))
    )
  )
)
